# Arduino_Header.net
KiCad netlist of a schematic drawn in Altium Designer
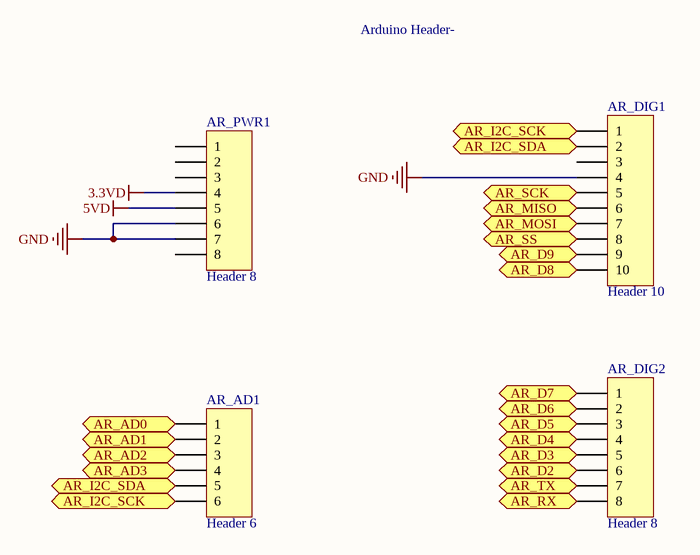
[diagram p0: Arduino_Header.SchDoc]

(export (version "E")
  (design (tool "Eeschema 10.0.6"))
  (components
    (comp (ref "AR_AD1")
      (value "Header 6")
      (footprint "HDR1X6")
      (description "Header, 6-Pin")
      (fields (field (name "PUBLISHER") "Altium Limited"))
      (libsource (lib "Miscellaneous Connectors") (part "Header 6"))
    )
    (comp (ref "AR_DIG1")
      (value "Header 10")
      (footprint "HDR1X10")
      (description "Header, 10-Pin")
      (fields (field (name "PUBLISHER") "Altium Limited"))
      (libsource (lib "Miscellaneous Connectors") (part "Header 10"))
    )
    (comp (ref "AR_DIG2")
      (value "Header 8")
      (footprint "HDR1X8")
      (description "Header, 8-Pin")
      (fields (field (name "PUBLISHER") "Altium Limited"))
      (libsource (lib "Miscellaneous Connectors") (part "Header 8"))
    )
    (comp (ref "AR_PWR1")
      (value "Header 8")
      (footprint "HDR1X8")
      (description "Header, 8-Pin")
      (fields (field (name "PUBLISHER") "Altium Limited"))
      (libsource (lib "Miscellaneous Connectors") (part "Header 8"))
    )
  )
  (nets
    (net (code "1") (name "/AR_AD0") (class "Default")
      (node (ref "AR_AD1") (pin "1") (pinfunction "1_1") (pintype "passive"))
    )
    (net (code "2") (name "/AR_AD1") (class "Default")
      (node (ref "AR_AD1") (pin "2") (pinfunction "2_2") (pintype "passive"))
    )
    (net (code "3") (name "/AR_AD2") (class "Default")
      (node (ref "AR_AD1") (pin "3") (pinfunction "3_3") (pintype "passive"))
    )
    (net (code "4") (name "/AR_AD3") (class "Default")
      (node (ref "AR_AD1") (pin "4") (pinfunction "4_4") (pintype "passive"))
    )
    (net (code "5") (name "/AR_D2") (class "Default")
      (node (ref "AR_DIG2") (pin "6") (pinfunction "6_6") (pintype "passive"))
    )
    (net (code "6") (name "/AR_D3") (class "Default")
      (node (ref "AR_DIG2") (pin "5") (pinfunction "5_5") (pintype "passive"))
    )
    (net (code "7") (name "/AR_D4") (class "Default")
      (node (ref "AR_DIG2") (pin "4") (pinfunction "4_4") (pintype "passive"))
    )
    (net (code "8") (name "/AR_D5") (class "Default")
      (node (ref "AR_DIG2") (pin "3") (pinfunction "3_3") (pintype "passive"))
    )
    (net (code "9") (name "/AR_D6") (class "Default")
      (node (ref "AR_DIG2") (pin "2") (pinfunction "2_2") (pintype "passive"))
    )
    (net (code "10") (name "/AR_D7") (class "Default")
      (node (ref "AR_DIG2") (pin "1") (pinfunction "1_1") (pintype "passive"))
    )
    (net (code "11") (name "/AR_D8") (class "Default")
      (node (ref "AR_DIG1") (pin "10") (pinfunction "10_10") (pintype "passive"))
    )
    (net (code "12") (name "/AR_D9") (class "Default")
      (node (ref "AR_DIG1") (pin "9") (pinfunction "9_9") (pintype "passive"))
    )
    (net (code "13") (name "/AR_I2C_SCK") (class "Default")
      (node (ref "AR_AD1") (pin "6") (pinfunction "6_6") (pintype "passive"))
      (node (ref "AR_DIG1") (pin "1") (pinfunction "1_1") (pintype "passive"))
    )
    (net (code "14") (name "/AR_I2C_SDA") (class "Default")
      (node (ref "AR_AD1") (pin "5") (pinfunction "5_5") (pintype "passive"))
      (node (ref "AR_DIG1") (pin "2") (pinfunction "2_2") (pintype "passive"))
    )
    (net (code "15") (name "/AR_MISO") (class "Default")
      (node (ref "AR_DIG1") (pin "6") (pinfunction "6_6") (pintype "passive"))
    )
    (net (code "16") (name "/AR_MOSI") (class "Default")
      (node (ref "AR_DIG1") (pin "7") (pinfunction "7_7") (pintype "passive"))
    )
    (net (code "17") (name "/AR_RX") (class "Default")
      (node (ref "AR_DIG2") (pin "8") (pinfunction "8_8") (pintype "passive"))
    )
    (net (code "18") (name "/AR_SCK") (class "Default")
      (node (ref "AR_DIG1") (pin "5") (pinfunction "5_5") (pintype "passive"))
    )
    (net (code "19") (name "/AR_SS") (class "Default")
      (node (ref "AR_DIG1") (pin "8") (pinfunction "8_8") (pintype "passive"))
    )
    (net (code "20") (name "/AR_TX") (class "Default")
      (node (ref "AR_DIG2") (pin "7") (pinfunction "7_7") (pintype "passive"))
    )
    (net (code "21") (name "3.3VD") (class "Default")
      (node (ref "AR_PWR1") (pin "4") (pinfunction "4_4") (pintype "passive"))
    )
    (net (code "22") (name "5VD") (class "Default")
      (node (ref "AR_PWR1") (pin "5") (pinfunction "5_5") (pintype "passive"))
    )
    (net (code "23") (name "GND") (class "Default")
      (node (ref "AR_DIG1") (pin "4") (pinfunction "4_4") (pintype "passive"))
      (node (ref "AR_PWR1") (pin "6") (pinfunction "6_6") (pintype "passive"))
      (node (ref "AR_PWR1") (pin "7") (pinfunction "7_7") (pintype "passive"))
    )
    (net (code "24") (name "unconnected-(AR_DIG1-Pad3)") (class "Default")
      (node (ref "AR_DIG1") (pin "3") (pinfunction "3_3") (pintype "passive"))
    )
    (net (code "25") (name "unconnected-(AR_PWR1-Pad1)") (class "Default")
      (node (ref "AR_PWR1") (pin "1") (pinfunction "1_1") (pintype "passive"))
    )
    (net (code "26") (name "unconnected-(AR_PWR1-Pad2)") (class "Default")
      (node (ref "AR_PWR1") (pin "2") (pinfunction "2_2") (pintype "passive"))
    )
    (net (code "27") (name "unconnected-(AR_PWR1-Pad3)") (class "Default")
      (node (ref "AR_PWR1") (pin "3") (pinfunction "3_3") (pintype "passive"))
    )
    (net (code "28") (name "unconnected-(AR_PWR1-Pad8)") (class "Default")
      (node (ref "AR_PWR1") (pin "8") (pinfunction "8_8") (pintype "passive"))
    )
  )
)
